# USB.net
KiCad netlist of a schematic drawn in Altium Designer
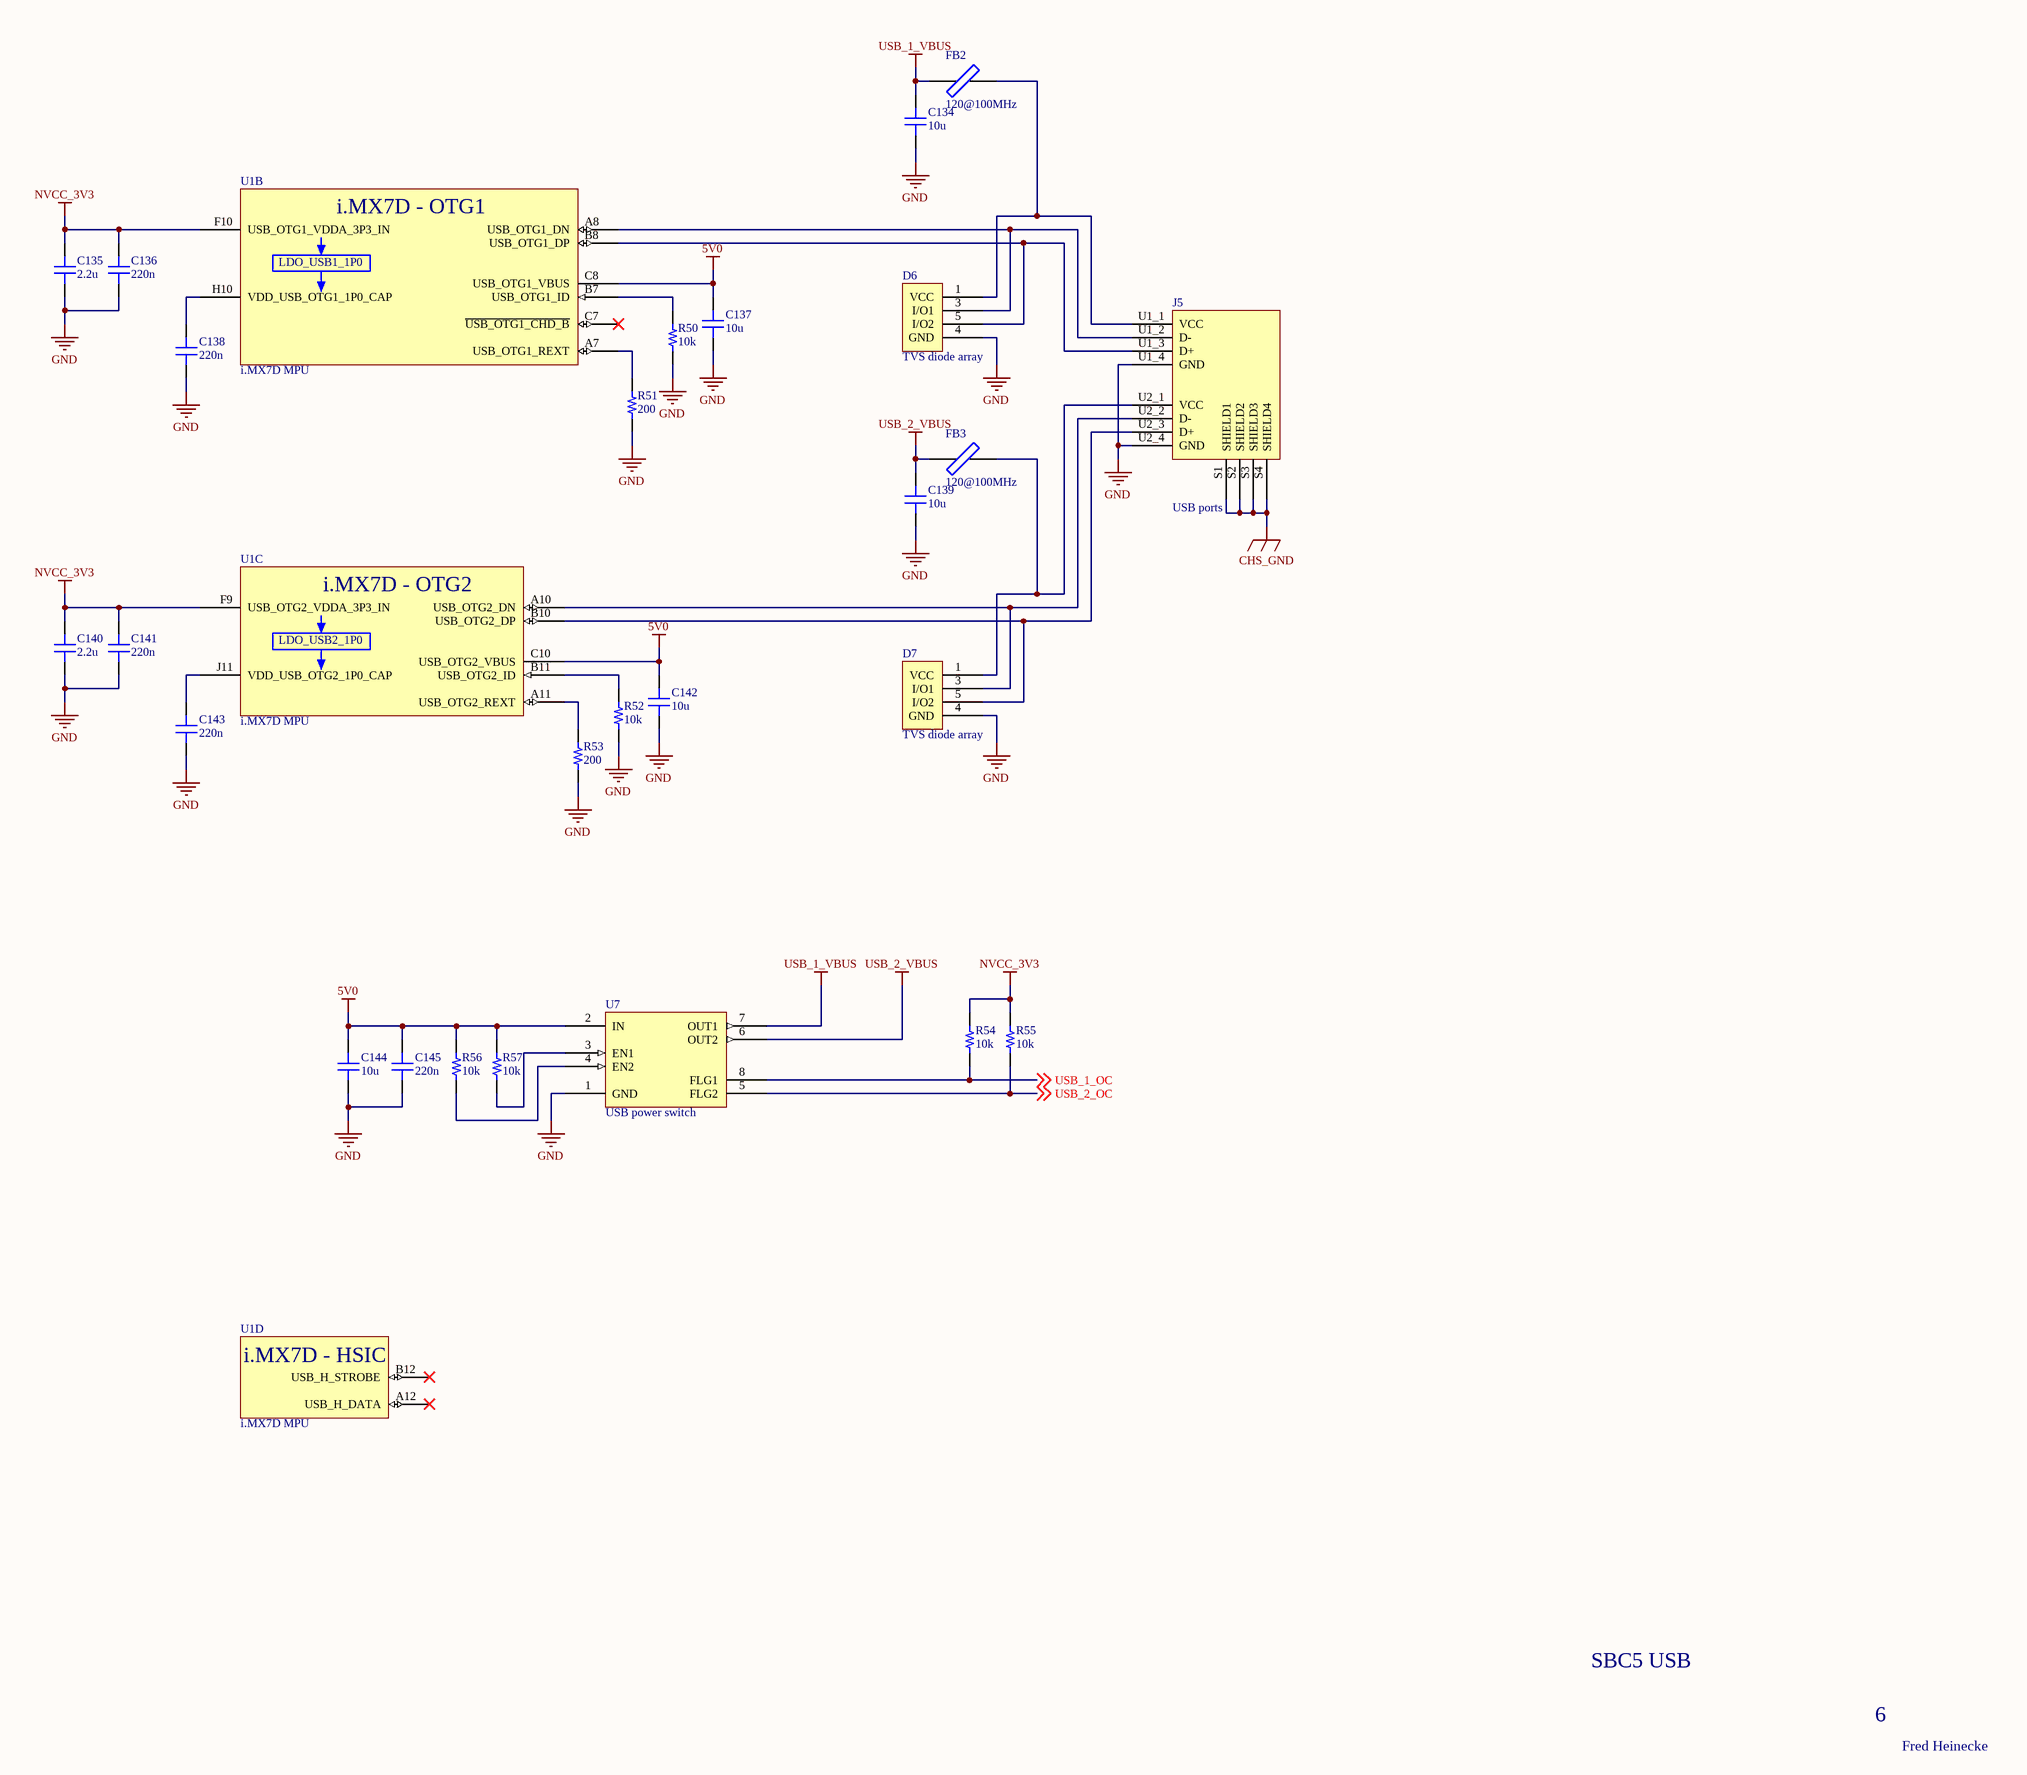
[diagram p0: USB.SchDoc]

(export (version "E")
  (design (tool "Eeschema 10.0.6"))
  (components
    (comp (ref "C134")
      (value "10u")
      (footprint "C0805")
      (fields
        (field (name "MANUFACTURER") "Samsung")
        (field (name "MANUFACTURER PART NUMBER") "CL21A106KOQNNNE")
        (field (name "TOLERANCE") "10%")
      )
      (libsource (lib "SBC5") (part "CL21A106KOQNNNE"))
    )
    (comp (ref "C135")
      (value "2.2u")
      (footprint "C0402")
      (description "TAIYO YUDEN         LMK105BJ225MV-F            CERAMIC CAPACITOR, 2.2UF, 10V, X5R, 20%, 0402")
      (fields
        (field (name "MANUFACTURER") "Taiyo Yuden")
        (field (name "MANUFACTURER PART NUMBER") "LMK105BJ225MV-F")
      )
      (libsource (lib "SBC5") (part "LMK105BJ225MV-F"))
    )
    (comp (ref "C136")
      (value "220n")
      (footprint "C0201")
      (description "Cap Ceramic Monolithic 0.22uF 16VDC 10% SMD Paper T/R")
      (fields
        (field (name "MANUFACTURER") "Murata")
        (field (name "MANUFACTURER PART NUMBER") "GRM033R61C224KE14D")
      )
      (libsource (lib "SBC5") (part "GRM033R61C224KE14D"))
    )
    (comp (ref "C137")
      (value "10u")
      (footprint "C0805")
      (fields
        (field (name "MANUFACTURER") "Samsung")
        (field (name "MANUFACTURER PART NUMBER") "CL21A106KOQNNNE")
        (field (name "TOLERANCE") "10%")
      )
      (libsource (lib "SBC5") (part "CL21A106KOQNNNE"))
    )
    (comp (ref "C138")
      (value "220n")
      (footprint "C0201")
      (description "Cap Ceramic Monolithic 0.22uF 16VDC 10% SMD Paper T/R")
      (fields
        (field (name "MANUFACTURER") "Murata")
        (field (name "MANUFACTURER PART NUMBER") "GRM033R61C224KE14D")
      )
      (libsource (lib "SBC5") (part "GRM033R61C224KE14D"))
    )
    (comp (ref "C139")
      (value "10u")
      (footprint "C0805")
      (fields
        (field (name "MANUFACTURER") "Samsung")
        (field (name "MANUFACTURER PART NUMBER") "CL21A106KOQNNNE")
        (field (name "TOLERANCE") "10%")
      )
      (libsource (lib "SBC5") (part "CL21A106KOQNNNE"))
    )
    (comp (ref "C140")
      (value "2.2u")
      (footprint "C0402")
      (description "TAIYO YUDEN         LMK105BJ225MV-F            CERAMIC CAPACITOR, 2.2UF, 10V, X5R, 20%, 0402")
      (fields
        (field (name "MANUFACTURER") "Taiyo Yuden")
        (field (name "MANUFACTURER PART NUMBER") "LMK105BJ225MV-F")
      )
      (libsource (lib "SBC5") (part "LMK105BJ225MV-F"))
    )
    (comp (ref "C141")
      (value "220n")
      (footprint "C0201")
      (description "Cap Ceramic Monolithic 0.22uF 16VDC 10% SMD Paper T/R")
      (fields
        (field (name "MANUFACTURER") "Murata")
        (field (name "MANUFACTURER PART NUMBER") "GRM033R61C224KE14D")
      )
      (libsource (lib "SBC5") (part "GRM033R61C224KE14D"))
    )
    (comp (ref "C142")
      (value "10u")
      (footprint "C0805")
      (fields
        (field (name "MANUFACTURER") "Samsung")
        (field (name "MANUFACTURER PART NUMBER") "CL21A106KOQNNNE")
        (field (name "TOLERANCE") "10%")
      )
      (libsource (lib "SBC5") (part "CL21A106KOQNNNE"))
    )
    (comp (ref "C143")
      (value "220n")
      (footprint "C0201")
      (description "Cap Ceramic Monolithic 0.22uF 16VDC 10% SMD Paper T/R")
      (fields
        (field (name "MANUFACTURER") "Murata")
        (field (name "MANUFACTURER PART NUMBER") "GRM033R61C224KE14D")
      )
      (libsource (lib "SBC5") (part "GRM033R61C224KE14D"))
    )
    (comp (ref "C144")
      (value "10u")
      (footprint "C0805")
      (fields
        (field (name "MANUFACTURER") "Samsung")
        (field (name "MANUFACTURER PART NUMBER") "CL21A106KOQNNNE")
        (field (name "TOLERANCE") "10%")
      )
      (libsource (lib "SBC5") (part "CL21A106KOQNNNE"))
    )
    (comp (ref "C145")
      (value "220n")
      (footprint "C0201")
      (description "Cap Ceramic Monolithic 0.22uF 16VDC 10% SMD Paper T/R")
      (fields
        (field (name "MANUFACTURER") "Murata")
        (field (name "MANUFACTURER PART NUMBER") "GRM033R61C224KE14D")
      )
      (libsource (lib "SBC5") (part "GRM033R61C224KE14D"))
    )
    (comp (ref "D6")
      (value "TVS diode array")
      (footprint "TPD2E001DRLR")
      (fields
        (field (name "MANUFACTURER") "Texas Instruments")
        (field (name "MANUFACTURER PART NUMBER") "TPD2E001DRLR")
      )
      (libsource (lib "SBC5") (part "TPD2E001DRLR"))
    )
    (comp (ref "D7")
      (value "TVS diode array")
      (footprint "TPD2E001DRLR")
      (fields
        (field (name "MANUFACTURER") "Texas Instruments")
        (field (name "MANUFACTURER PART NUMBER") "TPD2E001DRLR")
      )
      (libsource (lib "SBC5") (part "TPD2E001DRLR"))
    )
    (comp (ref "FB2")
      (value "120@100MHz")
      (footprint "L0402")
      (fields
        (field (name "MANUFACTURER") "Murata")
        (field (name "MANUFACTURER PART NUMBER") "BLM15PD121SN1D")
        (field (name "TOLERANCE") "25%")
      )
      (libsource (lib "SBC5") (part "BLM15PD121SN1D"))
    )
    (comp (ref "FB3")
      (value "120@100MHz")
      (footprint "L0402")
      (fields
        (field (name "MANUFACTURER") "Murata")
        (field (name "MANUFACTURER PART NUMBER") "BLM15PD121SN1D")
        (field (name "TOLERANCE") "25%")
      )
      (libsource (lib "SBC5") (part "BLM15PD121SN1D"))
    )
    (comp (ref "J5")
      (value "USB ports")
      (footprint "UJ2-ADH-1-TH")
      (description "CONN RCPT USB2.0 TYPEA STACK R/A")
      (fields (field (name "MANUFACTURER") "CUI") (field (name "MANUFACTURER PART NUMBER") "UJ2-ADH-1-TH"))
      (libsource (lib "SBC5") (part "UJ2-ADH-1-TH"))
    )
    (comp (ref "R50")
      (value "10k")
      (footprint "R0201")
      (description "RES 10K OHM 1% 1/20W 0201")
      (fields
        (field (name "MANUFACTURER") "Stackpole Electronics")
        (field (name "MANUFACTURER PART NUMBER") "RMCF0201FT10K0")
      )
      (libsource (lib "SBC5") (part "RMCF0201FT10K0"))
    )
    (comp (ref "R51")
      (value "200")
      (footprint "R0402")
      (description "Res Thick Film 0402 200 Ohm 1% 1/10W ±100ppm/°C Molded SMD Punched Carrier T/R")
      (fields
        (field (name "MANUFACTURER") "Panasonic")
        (field (name "MANUFACTURER PART NUMBER") "ERJ-2RKF2000X")
      )
      (libsource (lib "SBC5") (part "ERJ-2RKF2000X"))
    )
    (comp (ref "R52")
      (value "10k")
      (footprint "R0201")
      (description "RES 10K OHM 1% 1/20W 0201")
      (fields
        (field (name "MANUFACTURER") "Stackpole Electronics")
        (field (name "MANUFACTURER PART NUMBER") "RMCF0201FT10K0")
      )
      (libsource (lib "SBC5") (part "RMCF0201FT10K0"))
    )
    (comp (ref "R53")
      (value "200")
      (footprint "R0402")
      (description "Res Thick Film 0402 200 Ohm 1% 1/10W ±100ppm/°C Molded SMD Punched Carrier T/R")
      (fields
        (field (name "MANUFACTURER") "Panasonic")
        (field (name "MANUFACTURER PART NUMBER") "ERJ-2RKF2000X")
      )
      (libsource (lib "SBC5") (part "ERJ-2RKF2000X"))
    )
    (comp (ref "R54")
      (value "10k")
      (footprint "R0201")
      (description "RES 10K OHM 1% 1/20W 0201")
      (fields
        (field (name "MANUFACTURER") "Stackpole Electronics")
        (field (name "MANUFACTURER PART NUMBER") "RMCF0201FT10K0")
      )
      (libsource (lib "SBC5") (part "RMCF0201FT10K0"))
    )
    (comp (ref "R55")
      (value "10k")
      (footprint "R0201")
      (description "RES 10K OHM 1% 1/20W 0201")
      (fields
        (field (name "MANUFACTURER") "Stackpole Electronics")
        (field (name "MANUFACTURER PART NUMBER") "RMCF0201FT10K0")
      )
      (libsource (lib "SBC5") (part "RMCF0201FT10K0"))
    )
    (comp (ref "R56")
      (value "10k")
      (footprint "R0201")
      (description "RES 10K OHM 1% 1/20W 0201")
      (fields
        (field (name "MANUFACTURER") "Stackpole Electronics")
        (field (name "MANUFACTURER PART NUMBER") "RMCF0201FT10K0")
      )
      (libsource (lib "SBC5") (part "RMCF0201FT10K0"))
    )
    (comp (ref "R57")
      (value "10k")
      (footprint "R0201")
      (description "RES 10K OHM 1% 1/20W 0201")
      (fields
        (field (name "MANUFACTURER") "Stackpole Electronics")
        (field (name "MANUFACTURER PART NUMBER") "RMCF0201FT10K0")
      )
      (libsource (lib "SBC5") (part "RMCF0201FT10K0"))
    )
    (comp (ref "U1")
      (value "i.MX7D MPU")
      (footprint "BGA541C75P25X25_1900X1900X140")
      (description "Heterogeneous Multicore Processing Architecture")
      (fields
        (field (name "MANUFACTURER") "NXP Freescale")
        (field (name "MANUFACTURER PART NUMBER") "MCIMX7D2DVM12SD")
      )
      (libsource (lib "SBC5") (part "MCIMX7D2DVM12SD"))
    )
    (comp (ref "U7")
      (value "USB power switch")
      (footprint "SO-8")
      (description "IC PWR SW USB 2CH 0.5A 8-SOIC")
      (fields (field (name "MANUFACTURER") "Diodes") (field (name "MANUFACTURER PART NUMBER") "AP2152SG-13"))
      (libsource (lib "SBC5") (part "AP2152SG-13"))
    )
  )
  (nets
    (net (code "1") (name "5V0") (class "Default")
      (node (ref "C137") (pin "2") (pinfunction "2_2") (pintype "passive"))
      (node (ref "C142") (pin "2") (pinfunction "2_2") (pintype "passive"))
      (node (ref "C144") (pin "2") (pinfunction "2_2") (pintype "passive"))
      (node (ref "C145") (pin "2") (pinfunction "2_2") (pintype "passive"))
      (node (ref "R56") (pin "2") (pinfunction "2_2") (pintype "passive"))
      (node (ref "R57") (pin "2") (pinfunction "2_2") (pintype "passive"))
      (node (ref "U1") (pin "C10") (pinfunction "USB_OTG2_VBUS_C10") (pintype "power_in"))
      (node (ref "U1") (pin "C8") (pinfunction "USB_OTG1_VBUS_C8") (pintype "power_in"))
      (node (ref "U7") (pin "2") (pinfunction "IN_2") (pintype "power_in"))
    )
    (net (code "2") (name "CHS_GND") (class "Default")
      (node (ref "J5") (pin "S1") (pinfunction "SHIELD1_S1") (pintype "passive"))
      (node (ref "J5") (pin "S2") (pinfunction "SHIELD2_S2") (pintype "passive"))
      (node (ref "J5") (pin "S3") (pinfunction "SHIELD3_S3") (pintype "passive"))
      (node (ref "J5") (pin "S4") (pinfunction "SHIELD4_S4") (pintype "passive"))
    )
    (net (code "3") (name "GND") (class "Default")
      (node (ref "C134") (pin "1") (pinfunction "1_1") (pintype "passive"))
      (node (ref "C135") (pin "1") (pinfunction "1_1") (pintype "passive"))
      (node (ref "C136") (pin "1") (pinfunction "1_1") (pintype "passive"))
      (node (ref "C137") (pin "1") (pinfunction "1_1") (pintype "passive"))
      (node (ref "C138") (pin "1") (pinfunction "1_1") (pintype "passive"))
      (node (ref "C139") (pin "1") (pinfunction "1_1") (pintype "passive"))
      (node (ref "C140") (pin "1") (pinfunction "1_1") (pintype "passive"))
      (node (ref "C141") (pin "1") (pinfunction "1_1") (pintype "passive"))
      (node (ref "C142") (pin "1") (pinfunction "1_1") (pintype "passive"))
      (node (ref "C143") (pin "1") (pinfunction "1_1") (pintype "passive"))
      (node (ref "C144") (pin "1") (pinfunction "1_1") (pintype "passive"))
      (node (ref "C145") (pin "1") (pinfunction "1_1") (pintype "passive"))
      (node (ref "D6") (pin "4") (pinfunction "GND_4") (pintype "passive"))
      (node (ref "D7") (pin "4") (pinfunction "GND_4") (pintype "passive"))
      (node (ref "J5") (pin "U1_4") (pinfunction "GND_U1_4") (pintype "passive"))
      (node (ref "J5") (pin "U2_4") (pinfunction "GND_U2_4") (pintype "passive"))
      (node (ref "R50") (pin "1") (pinfunction "1_1") (pintype "passive"))
      (node (ref "R51") (pin "1") (pinfunction "1_1") (pintype "passive"))
      (node (ref "R52") (pin "1") (pinfunction "1_1") (pintype "passive"))
      (node (ref "R53") (pin "1") (pinfunction "1_1") (pintype "passive"))
      (node (ref "U7") (pin "1") (pinfunction "GND_1") (pintype "passive"))
    )
    (net (code "4") (name "NVCC_3V3") (class "Default")
      (node (ref "C135") (pin "2") (pinfunction "2_2") (pintype "passive"))
      (node (ref "C136") (pin "2") (pinfunction "2_2") (pintype "passive"))
      (node (ref "C140") (pin "2") (pinfunction "2_2") (pintype "passive"))
      (node (ref "C141") (pin "2") (pinfunction "2_2") (pintype "passive"))
      (node (ref "R54") (pin "2") (pinfunction "2_2") (pintype "passive"))
      (node (ref "R55") (pin "2") (pinfunction "2_2") (pintype "passive"))
      (node (ref "U1") (pin "F10") (pinfunction "USB_OTG1_VDDA_3P3_IN_F10") (pintype "power_in"))
      (node (ref "U1") (pin "F9") (pinfunction "USB_OTG2_VDDA_3P3_IN_F9") (pintype "power_in"))
    )
    (net (code "5") (name "Net-(D6-I{slash}O1)") (class "Default")
      (node (ref "D6") (pin "3") (pinfunction "I/O1_3") (pintype "passive"))
      (node (ref "J5") (pin "U1_2") (pinfunction "D-_U1_2") (pintype "passive"))
      (node (ref "U1") (pin "A8") (pinfunction "USB_OTG1_DN_A8") (pintype "bidirectional"))
    )
    (net (code "6") (name "Net-(D6-I{slash}O2)") (class "Default")
      (node (ref "D6") (pin "5") (pinfunction "I/O2_5") (pintype "passive"))
      (node (ref "J5") (pin "U1_3") (pinfunction "D+_U1_3") (pintype "passive"))
      (node (ref "U1") (pin "B8") (pinfunction "USB_OTG1_DP_B8") (pintype "bidirectional"))
    )
    (net (code "7") (name "Net-(D6-VCC)") (class "Default")
      (node (ref "D6") (pin "1") (pinfunction "VCC_1") (pintype "passive"))
      (node (ref "FB2") (pin "2") (pinfunction "2_2") (pintype "passive"))
      (node (ref "J5") (pin "U1_1") (pinfunction "VCC_U1_1") (pintype "passive"))
    )
    (net (code "8") (name "Net-(D7-I{slash}O1)") (class "Default")
      (node (ref "D7") (pin "3") (pinfunction "I/O1_3") (pintype "passive"))
      (node (ref "J5") (pin "U2_2") (pinfunction "D-_U2_2") (pintype "passive"))
      (node (ref "U1") (pin "A10") (pinfunction "USB_OTG2_DN_A10") (pintype "bidirectional"))
    )
    (net (code "9") (name "Net-(D7-I{slash}O2)") (class "Default")
      (node (ref "D7") (pin "5") (pinfunction "I/O2_5") (pintype "passive"))
      (node (ref "J5") (pin "U2_3") (pinfunction "D+_U2_3") (pintype "passive"))
      (node (ref "U1") (pin "B10") (pinfunction "USB_OTG2_DP_B10") (pintype "bidirectional"))
    )
    (net (code "10") (name "Net-(D7-VCC)") (class "Default")
      (node (ref "D7") (pin "1") (pinfunction "VCC_1") (pintype "passive"))
      (node (ref "FB3") (pin "2") (pinfunction "2_2") (pintype "passive"))
      (node (ref "J5") (pin "U2_1") (pinfunction "VCC_U2_1") (pintype "passive"))
    )
    (net (code "11") (name "Net-(U1B-USB_OTG1_ID)") (class "Default")
      (node (ref "R50") (pin "2") (pinfunction "2_2") (pintype "passive"))
      (node (ref "U1") (pin "B7") (pinfunction "USB_OTG1_ID_B7") (pintype "input"))
    )
    (net (code "12") (name "Net-(U1B-USB_OTG1_REXT)") (class "Default")
      (node (ref "R51") (pin "2") (pinfunction "2_2") (pintype "passive"))
      (node (ref "U1") (pin "A7") (pinfunction "USB_OTG1_REXT_A7") (pintype "bidirectional"))
    )
    (net (code "13") (name "Net-(U1B-VDD_USB_OTG1_1P0_CAP)") (class "Default")
      (node (ref "C138") (pin "2") (pinfunction "2_2") (pintype "passive"))
      (node (ref "U1") (pin "H10") (pinfunction "VDD_USB_OTG1_1P0_CAP_H10") (pintype "power_in"))
    )
    (net (code "14") (name "Net-(U1C-USB_OTG2_ID)") (class "Default")
      (node (ref "R52") (pin "2") (pinfunction "2_2") (pintype "passive"))
      (node (ref "U1") (pin "B11") (pinfunction "USB_OTG2_ID_B11") (pintype "input"))
    )
    (net (code "15") (name "Net-(U1C-USB_OTG2_REXT)") (class "Default")
      (node (ref "R53") (pin "2") (pinfunction "2_2") (pintype "passive"))
      (node (ref "U1") (pin "A11") (pinfunction "USB_OTG2_REXT_A11") (pintype "bidirectional"))
    )
    (net (code "16") (name "Net-(U1C-VDD_USB_OTG2_1P0_CAP)") (class "Default")
      (node (ref "C143") (pin "2") (pinfunction "2_2") (pintype "passive"))
      (node (ref "U1") (pin "J11") (pinfunction "VDD_USB_OTG2_1P0_CAP_J11") (pintype "power_in"))
    )
    (net (code "17") (name "Net-(U7-EN1)") (class "Default")
      (node (ref "R57") (pin "1") (pinfunction "1_1") (pintype "passive"))
      (node (ref "U7") (pin "3") (pinfunction "EN1_3") (pintype "input"))
    )
    (net (code "18") (name "Net-(U7-EN2)") (class "Default")
      (node (ref "R56") (pin "1") (pinfunction "1_1") (pintype "passive"))
      (node (ref "U7") (pin "4") (pinfunction "EN2_4") (pintype "input"))
    )
    (net (code "19") (name "USB_1_OC") (class "Default")
      (node (ref "R54") (pin "1") (pinfunction "1_1") (pintype "passive"))
      (node (ref "U7") (pin "8") (pinfunction "FLG1_8") (pintype "open_collector"))
    )
    (net (code "20") (name "USB_1_VBUS") (class "Default")
      (node (ref "C134") (pin "2") (pinfunction "2_2") (pintype "passive"))
      (node (ref "FB2") (pin "1") (pinfunction "1_1") (pintype "passive"))
      (node (ref "U7") (pin "7") (pinfunction "OUT1_7") (pintype "output"))
    )
    (net (code "21") (name "USB_2_OC") (class "Default")
      (node (ref "R55") (pin "1") (pinfunction "1_1") (pintype "passive"))
      (node (ref "U7") (pin "5") (pinfunction "FLG2_5") (pintype "open_collector"))
    )
    (net (code "22") (name "USB_2_VBUS") (class "Default")
      (node (ref "C139") (pin "2") (pinfunction "2_2") (pintype "passive"))
      (node (ref "FB3") (pin "1") (pinfunction "1_1") (pintype "passive"))
      (node (ref "U7") (pin "6") (pinfunction "OUT2_6") (pintype "output"))
    )
    (net (code "23") (name "unconnected-(U1B-~{USB_OTG1_CHD_B}-PadC7)") (class "Default")
      (node (ref "U1") (pin "C7") (pinfunction "~{USB_OTG1_CHD_B}_C7") (pintype "bidirectional+no_connect"))
    )
    (net (code "24") (name "unconnected-(U1D-USB_H_DATA-PadA12)") (class "Default")
      (node (ref "U1") (pin "A12") (pinfunction "USB_H_DATA_A12") (pintype "bidirectional+no_connect"))
    )
    (net (code "25") (name "unconnected-(U1D-USB_H_STROBE-PadB12)") (class "Default")
      (node (ref "U1") (pin "B12") (pinfunction "USB_H_STROBE_B12") (pintype "bidirectional+no_connect"))
    )
  )
)
